# S2ER13.net
KiCad netlist of a schematic drawn in EAGLE
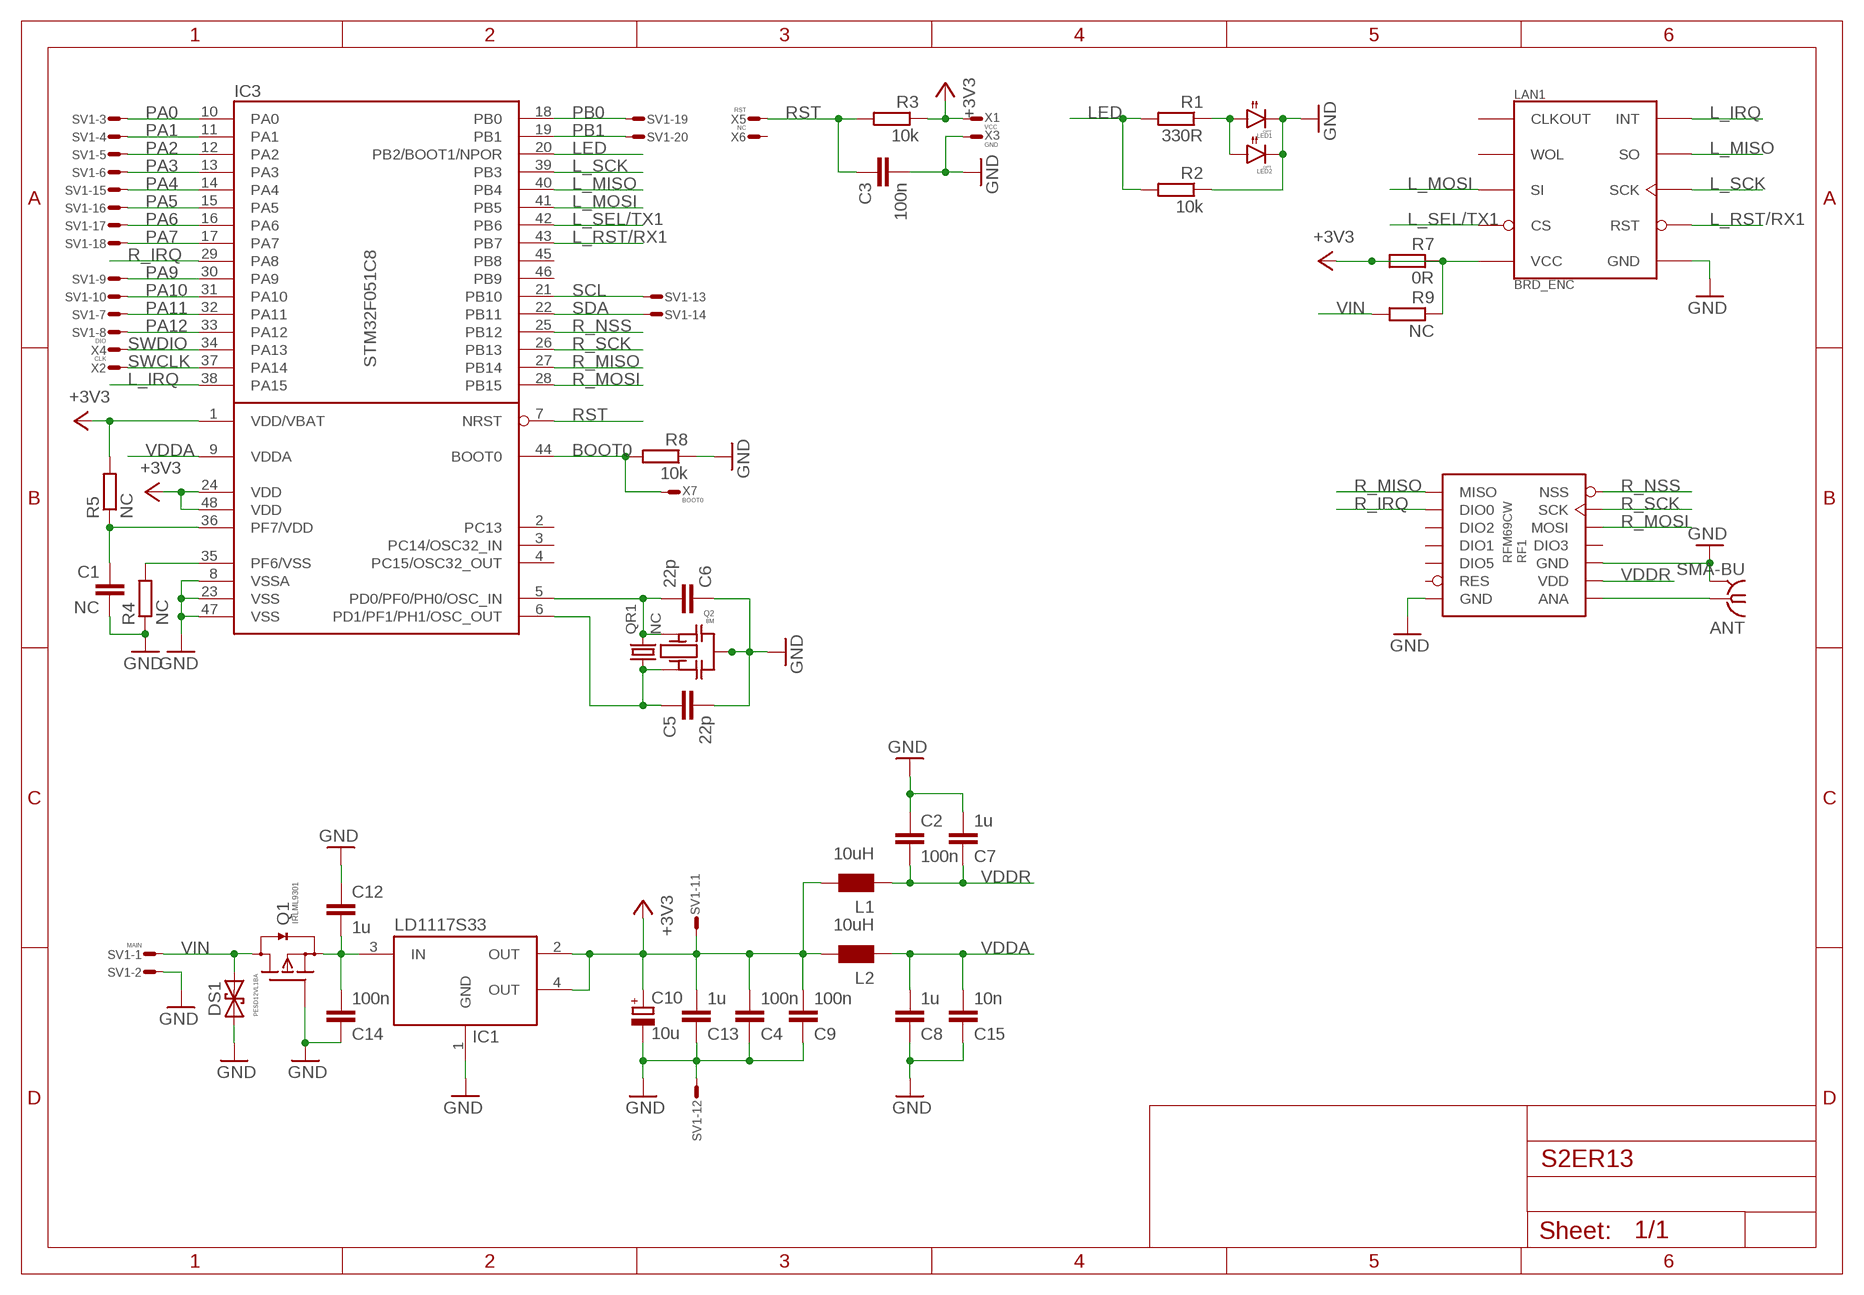
[diagram p0: schematic, sheet 1]

(export (version "E")
  (design (tool "Eeschema 10.0.6"))
  (components
    (comp (ref "ANT")
      (value "SMA-BU")
      (footprint "eagle-import:BU-SMA-V")
      (libsource (lib "eagle-import") (part "SMA-BU"))
    )
    (comp (ref "C1")
      (value "NC")
      (footprint "eagle-import:0603")
      (libsource (lib "eagle-import") (part "C0603"))
    )
    (comp (ref "C2")
      (value "100n")
      (footprint "eagle-import:0603")
      (libsource (lib "eagle-import") (part "C0603"))
    )
    (comp (ref "C3")
      (value "100n")
      (footprint "eagle-import:0603")
      (libsource (lib "eagle-import") (part "C0603"))
    )
    (comp (ref "C4")
      (value "100n")
      (footprint "eagle-import:0603")
      (libsource (lib "eagle-import") (part "C0603"))
    )
    (comp (ref "C5")
      (value "22p")
      (footprint "eagle-import:0603")
      (libsource (lib "eagle-import") (part "C0603"))
    )
    (comp (ref "C6")
      (value "22p")
      (footprint "eagle-import:0603")
      (libsource (lib "eagle-import") (part "C0603"))
    )
    (comp (ref "C7")
      (value "1u")
      (footprint "eagle-import:0603")
      (libsource (lib "eagle-import") (part "C0603"))
    )
    (comp (ref "C8")
      (value "1u")
      (footprint "eagle-import:0603")
      (libsource (lib "eagle-import") (part "C0603"))
    )
    (comp (ref "C9")
      (value "100n")
      (footprint "eagle-import:0603")
      (libsource (lib "eagle-import") (part "C0603"))
    )
    (comp (ref "C10")
      (value "10u")
      (footprint "eagle-import:SMC_A")
      (libsource (lib "eagle-import") (part "C_POLSMCA"))
    )
    (comp (ref "C12")
      (value "1u")
      (footprint "eagle-import:0603")
      (libsource (lib "eagle-import") (part "C0603"))
    )
    (comp (ref "C13")
      (value "1u")
      (footprint "eagle-import:0603")
      (libsource (lib "eagle-import") (part "C0603"))
    )
    (comp (ref "C14")
      (value "100n")
      (footprint "eagle-import:0603")
      (libsource (lib "eagle-import") (part "C0603"))
    )
    (comp (ref "C15")
      (value "10n")
      (footprint "eagle-import:0603")
      (libsource (lib "eagle-import") (part "C0603"))
    )
    (comp (ref "DS1")
      (value "PESD12VL1BA")
      (footprint "eagle-import:SOD323")
      (libsource (lib "eagle-import") (part "TVS-U323"))
    )
    (comp (ref "IC1")
      (value "LD1117S33")
      (footprint "eagle-import:SOT223")
      (libsource (lib "eagle-import") (part "LDO_4P"))
    )
    (comp (ref "IC3")
      (value "STM32F051C8")
      (footprint "eagle-import:LQFP48")
      (libsource (lib "eagle-import") (part "STM32_LQFP48"))
    )
    (comp (ref "L1")
      (value "10uH")
      (footprint "eagle-import:0603")
      (libsource (lib "eagle-import") (part "L0603"))
    )
    (comp (ref "L2")
      (value "10uH")
      (footprint "eagle-import:0603")
      (libsource (lib "eagle-import") (part "L0603"))
    )
    (comp (ref "LAN1")
      (value "BRD_ENC")
      (footprint "eagle-import:BRD_ENC")
      (libsource (lib "eagle-import") (part "BRD_ENC"))
    )
    (comp (ref "LED1")
      (value "OPT")
      (footprint "eagle-import:T1-3_4")
      (libsource (lib "eagle-import") (part "LEDT134"))
    )
    (comp (ref "LED2")
      (value "OPT")
      (footprint "eagle-import:1206")
      (libsource (lib "eagle-import") (part "LED1206"))
    )
    (comp (ref "Q1")
      (value "IRLML9301")
      (footprint "eagle-import:SOT23")
      (libsource (lib "eagle-import") (part "FET-PDSOT23"))
    )
    (comp (ref "Q2")
      (value "8M")
      (footprint "eagle-import:CSTCE")
      (libsource (lib "eagle-import") (part "QRCE"))
    )
    (comp (ref "QR1")
      (value "NC")
      (footprint "eagle-import:ABS07")
      (libsource (lib "eagle-import") (part "QABS07"))
    )
    (comp (ref "R1")
      (value "330R")
      (footprint "eagle-import:0603")
      (libsource (lib "eagle-import") (part "R0603"))
    )
    (comp (ref "R2")
      (value "10k")
      (footprint "eagle-import:0603")
      (libsource (lib "eagle-import") (part "R0603"))
    )
    (comp (ref "R3")
      (value "10k")
      (footprint "eagle-import:0603")
      (libsource (lib "eagle-import") (part "R0603"))
    )
    (comp (ref "R4")
      (value "NC")
      (footprint "eagle-import:0603")
      (libsource (lib "eagle-import") (part "R0603"))
    )
    (comp (ref "R5")
      (value "NC")
      (footprint "eagle-import:0603")
      (libsource (lib "eagle-import") (part "R0603"))
    )
    (comp (ref "R7")
      (value "0R")
      (footprint "eagle-import:0603")
      (libsource (lib "eagle-import") (part "R0603"))
    )
    (comp (ref "R8")
      (value "10k")
      (footprint "eagle-import:0603")
      (libsource (lib "eagle-import") (part "R0603"))
    )
    (comp (ref "R9")
      (value "NC")
      (footprint "eagle-import:0603")
      (libsource (lib "eagle-import") (part "R0603"))
    )
    (comp (ref "RF1")
      (value "RFM69CW")
      (footprint "eagle-import:RFM69CW")
      (libsource (lib "eagle-import") (part "RFM69CWS1-868-"))
    )
    (comp (ref "SV1")
      (value "MAIN")
      (footprint "eagle-import:ML20LS")
      (libsource (lib "eagle-import") (part "ML20?ELS"))
    )
    (comp (ref "X1")
      (value "VCC")
      (footprint "eagle-import:T1.6_0.9")
      (libsource (lib "eagle-import") (part "WIREPADT1.6/0.9"))
    )
    (comp (ref "X2")
      (value "CLK")
      (footprint "eagle-import:T1.6_0.9")
      (libsource (lib "eagle-import") (part "WIREPADT1.6/0.9"))
    )
    (comp (ref "X3")
      (value "GND")
      (footprint "eagle-import:T1.6_0.9")
      (libsource (lib "eagle-import") (part "WIREPADT1.6/0.9"))
    )
    (comp (ref "X4")
      (value "DIO")
      (footprint "eagle-import:T1.6_0.9")
      (libsource (lib "eagle-import") (part "WIREPADT1.6/0.9"))
    )
    (comp (ref "X5")
      (value "RST")
      (footprint "eagle-import:T1.6_0.9")
      (libsource (lib "eagle-import") (part "WIREPADT1.6/0.9"))
    )
    (comp (ref "X6")
      (value "NC")
      (footprint "eagle-import:T1.6_0.9")
      (libsource (lib "eagle-import") (part "WIREPADT1.6/0.9"))
    )
    (comp (ref "X7")
      (value "BOOT0")
      (footprint "eagle-import:T1.6_0.9")
      (libsource (lib "eagle-import") (part "WIREPADT1.6/0.9"))
    )
  )
  (nets
    (net (code "1") (name "+3V3") (class "Default")
      (node (ref "C10") (pin "+") (pinfunction "+_+") (pintype "passive"))
      (node (ref "C13") (pin "2") (pinfunction "2_2") (pintype "passive"))
      (node (ref "C4") (pin "2") (pinfunction "2_2") (pintype "passive"))
      (node (ref "C9") (pin "2") (pinfunction "2_2") (pintype "passive"))
      (node (ref "IC1") (pin "2") (pinfunction "OUT_2") (pintype "bidirectional"))
      (node (ref "IC1") (pin "4") (pinfunction "OUT_4") (pintype "bidirectional"))
      (node (ref "IC3") (pin "1") (pinfunction "VDD/VBAT_1") (pintype "bidirectional"))
      (node (ref "IC3") (pin "24") (pinfunction "VDD_24") (pintype "bidirectional"))
      (node (ref "IC3") (pin "48") (pinfunction "VDD_48") (pintype "bidirectional"))
      (node (ref "L1") (pin "2") (pinfunction "2_2") (pintype "passive"))
      (node (ref "L2") (pin "2") (pinfunction "2_2") (pintype "passive"))
      (node (ref "LAN1") (pin "P$9") (pinfunction "VCC_P$9") (pintype "bidirectional"))
      (node (ref "R3") (pin "1") (pinfunction "1_1") (pintype "passive"))
      (node (ref "R5") (pin "2") (pinfunction "2_2") (pintype "passive"))
      (node (ref "R7") (pin "1") (pinfunction "1_1") (pintype "passive"))
      (node (ref "R7") (pin "2") (pinfunction "2_2") (pintype "passive"))
      (node (ref "R9") (pin "1") (pinfunction "1_1") (pintype "passive"))
      (node (ref "SV1") (pin "P$11") (pinfunction "S_P$11") (pintype "passive"))
      (node (ref "X1") (pin "1") (pinfunction "S_1") (pintype "passive"))
    )
    (net (code "2") (name "/BOOT0") (class "Default")
      (node (ref "IC3") (pin "44") (pinfunction "BOOT0_44") (pintype "bidirectional"))
      (node (ref "R8") (pin "2") (pinfunction "2_2") (pintype "passive"))
      (node (ref "X7") (pin "1") (pinfunction "S_1") (pintype "passive"))
    )
    (net (code "3") (name "/LED") (class "Default")
      (node (ref "IC3") (pin "20") (pinfunction "PB2/BOOT1/NPOR_20") (pintype "bidirectional"))
      (node (ref "R1") (pin "2") (pinfunction "2_2") (pintype "passive"))
      (node (ref "R2") (pin "2") (pinfunction "2_2") (pintype "passive"))
    )
    (net (code "4") (name "/L_IRQ") (class "Default")
      (node (ref "IC3") (pin "38") (pinfunction "PA15_38") (pintype "bidirectional"))
      (node (ref "LAN1") (pin "P$2") (pinfunction "INT_P$2") (pintype "open_collector"))
    )
    (net (code "5") (name "/L_MISO") (class "Default")
      (node (ref "IC3") (pin "40") (pinfunction "PB4_40") (pintype "bidirectional"))
      (node (ref "LAN1") (pin "P$4") (pinfunction "SO_P$4") (pintype "output"))
    )
    (net (code "6") (name "/L_MOSI") (class "Default")
      (node (ref "IC3") (pin "41") (pinfunction "PB5_41") (pintype "bidirectional"))
      (node (ref "LAN1") (pin "P$5") (pinfunction "SI_P$5") (pintype "input"))
    )
    (net (code "7") (name "/L_RST{slash}RX1") (class "Default")
      (node (ref "IC3") (pin "43") (pinfunction "PB7_43") (pintype "bidirectional"))
      (node (ref "LAN1") (pin "P$8") (pinfunction "RST_P$8") (pintype "bidirectional"))
    )
    (net (code "8") (name "/L_SCK") (class "Default")
      (node (ref "IC3") (pin "39") (pinfunction "PB3_39") (pintype "bidirectional"))
      (node (ref "LAN1") (pin "P$6") (pinfunction "SCK_P$6") (pintype "input"))
    )
    (net (code "9") (name "/L_SEL{slash}TX1") (class "Default")
      (node (ref "IC3") (pin "42") (pinfunction "PB6_42") (pintype "bidirectional"))
      (node (ref "LAN1") (pin "P$7") (pinfunction "CS_P$7") (pintype "input"))
    )
    (net (code "10") (name "/PA0") (class "Default")
      (node (ref "IC3") (pin "10") (pinfunction "PA0_10") (pintype "bidirectional"))
      (node (ref "SV1") (pin "P$3") (pinfunction "S_P$3") (pintype "passive"))
    )
    (net (code "11") (name "/PA1") (class "Default")
      (node (ref "IC3") (pin "11") (pinfunction "PA1_11") (pintype "bidirectional"))
      (node (ref "SV1") (pin "P$4") (pinfunction "S_P$4") (pintype "passive"))
    )
    (net (code "12") (name "/PA2") (class "Default")
      (node (ref "IC3") (pin "12") (pinfunction "PA2_12") (pintype "bidirectional"))
      (node (ref "SV1") (pin "P$5") (pinfunction "S_P$5") (pintype "passive"))
    )
    (net (code "13") (name "/PA3") (class "Default")
      (node (ref "IC3") (pin "13") (pinfunction "PA3_13") (pintype "bidirectional"))
      (node (ref "SV1") (pin "P$6") (pinfunction "S_P$6") (pintype "passive"))
    )
    (net (code "14") (name "/PA4") (class "Default")
      (node (ref "IC3") (pin "14") (pinfunction "PA4_14") (pintype "bidirectional"))
      (node (ref "SV1") (pin "P$15") (pinfunction "S_P$15") (pintype "passive"))
    )
    (net (code "15") (name "/PA5") (class "Default")
      (node (ref "IC3") (pin "15") (pinfunction "PA5_15") (pintype "bidirectional"))
      (node (ref "SV1") (pin "P$16") (pinfunction "S_P$16") (pintype "passive"))
    )
    (net (code "16") (name "/PA6") (class "Default")
      (node (ref "IC3") (pin "16") (pinfunction "PA6_16") (pintype "bidirectional"))
      (node (ref "SV1") (pin "P$17") (pinfunction "S_P$17") (pintype "passive"))
    )
    (net (code "17") (name "/PA7") (class "Default")
      (node (ref "IC3") (pin "17") (pinfunction "PA7_17") (pintype "bidirectional"))
      (node (ref "SV1") (pin "P$18") (pinfunction "S_P$18") (pintype "passive"))
    )
    (net (code "18") (name "/PA9") (class "Default")
      (node (ref "IC3") (pin "30") (pinfunction "PA9_30") (pintype "bidirectional"))
      (node (ref "SV1") (pin "P$9") (pinfunction "S_P$9") (pintype "passive"))
    )
    (net (code "19") (name "/PA10") (class "Default")
      (node (ref "IC3") (pin "31") (pinfunction "PA10_31") (pintype "bidirectional"))
      (node (ref "SV1") (pin "P$10") (pinfunction "S_P$10") (pintype "passive"))
    )
    (net (code "20") (name "/PA11") (class "Default")
      (node (ref "IC3") (pin "32") (pinfunction "PA11_32") (pintype "bidirectional"))
      (node (ref "SV1") (pin "P$7") (pinfunction "S_P$7") (pintype "passive"))
    )
    (net (code "21") (name "/PA12") (class "Default")
      (node (ref "IC3") (pin "33") (pinfunction "PA12_33") (pintype "bidirectional"))
      (node (ref "SV1") (pin "P$8") (pinfunction "S_P$8") (pintype "passive"))
    )
    (net (code "22") (name "/PB0") (class "Default")
      (node (ref "IC3") (pin "18") (pinfunction "PB0_18") (pintype "bidirectional"))
      (node (ref "SV1") (pin "P$19") (pinfunction "S_P$19") (pintype "passive"))
    )
    (net (code "23") (name "/PB1") (class "Default")
      (node (ref "IC3") (pin "19") (pinfunction "PB1_19") (pintype "bidirectional"))
      (node (ref "SV1") (pin "P$20") (pinfunction "S_P$20") (pintype "passive"))
    )
    (net (code "24") (name "/RST") (class "Default")
      (node (ref "C3") (pin "1") (pinfunction "1_1") (pintype "passive"))
      (node (ref "IC3") (pin "7") (pinfunction "NRST_7") (pintype "bidirectional"))
      (node (ref "R3") (pin "2") (pinfunction "2_2") (pintype "passive"))
      (node (ref "X5") (pin "1") (pinfunction "S_1") (pintype "passive"))
    )
    (net (code "25") (name "/R_IRQ") (class "Default")
      (node (ref "IC3") (pin "29") (pinfunction "PA8_29") (pintype "bidirectional"))
      (node (ref "RF1") (pin "DIO0") (pinfunction "DIO0_DIO0") (pintype "bidirectional"))
    )
    (net (code "26") (name "/R_MISO") (class "Default")
      (node (ref "IC3") (pin "27") (pinfunction "PB14_27") (pintype "bidirectional"))
      (node (ref "RF1") (pin "MISO") (pinfunction "MISO_MISO") (pintype "output"))
    )
    (net (code "27") (name "/R_MOSI") (class "Default")
      (node (ref "IC3") (pin "28") (pinfunction "PB15_28") (pintype "bidirectional"))
      (node (ref "RF1") (pin "MOSI") (pinfunction "MOSI_MOSI") (pintype "input"))
    )
    (net (code "28") (name "/R_NSS") (class "Default")
      (node (ref "IC3") (pin "25") (pinfunction "PB12_25") (pintype "bidirectional"))
      (node (ref "RF1") (pin "NSS") (pinfunction "NSS_NSS") (pintype "input"))
    )
    (net (code "29") (name "/R_SCK") (class "Default")
      (node (ref "IC3") (pin "26") (pinfunction "PB13_26") (pintype "bidirectional"))
      (node (ref "RF1") (pin "SCK") (pinfunction "SCK_SCK") (pintype "input"))
    )
    (net (code "30") (name "/SCL") (class "Default")
      (node (ref "IC3") (pin "21") (pinfunction "PB10_21") (pintype "bidirectional"))
      (node (ref "SV1") (pin "P$13") (pinfunction "S_P$13") (pintype "passive"))
    )
    (net (code "31") (name "/SDA") (class "Default")
      (node (ref "IC3") (pin "22") (pinfunction "PB11_22") (pintype "bidirectional"))
      (node (ref "SV1") (pin "P$14") (pinfunction "S_P$14") (pintype "passive"))
    )
    (net (code "32") (name "/SWCLK") (class "Default")
      (node (ref "IC3") (pin "37") (pinfunction "PA14_37") (pintype "bidirectional"))
      (node (ref "X2") (pin "1") (pinfunction "S_1") (pintype "passive"))
    )
    (net (code "33") (name "/SWDIO") (class "Default")
      (node (ref "IC3") (pin "34") (pinfunction "PA13_34") (pintype "bidirectional"))
      (node (ref "X4") (pin "1") (pinfunction "S_1") (pintype "passive"))
    )
    (net (code "34") (name "/VDDA") (class "Default")
      (node (ref "C15") (pin "2") (pinfunction "2_2") (pintype "passive"))
      (node (ref "C8") (pin "2") (pinfunction "2_2") (pintype "passive"))
      (node (ref "IC3") (pin "9") (pinfunction "VDDA_9") (pintype "bidirectional"))
      (node (ref "L2") (pin "1") (pinfunction "1_1") (pintype "passive"))
    )
    (net (code "35") (name "/VDDR") (class "Default")
      (node (ref "C2") (pin "2") (pinfunction "2_2") (pintype "passive"))
      (node (ref "C7") (pin "1") (pinfunction "1_1") (pintype "passive"))
      (node (ref "L1") (pin "1") (pinfunction "1_1") (pintype "passive"))
      (node (ref "RF1") (pin "VDD") (pinfunction "VDD_VDD") (pintype "power_in"))
    )
    (net (code "36") (name "/VIN") (class "Default")
      (node (ref "DS1") (pin "C") (pinfunction "2_C") (pintype "passive"))
      (node (ref "Q1") (pin "3") (pinfunction "D_3") (pintype "passive"))
      (node (ref "R9") (pin "2") (pinfunction "2_2") (pintype "passive"))
      (node (ref "SV1") (pin "P$1") (pinfunction "S_P$1") (pintype "passive"))
    )
    (net (code "37") (name "GND") (class "Default")
      (node (ref "ANT") (pin "2") (pinfunction "2_2") (pintype "passive"))
      (node (ref "ANT") (pin "3") (pinfunction "2_3") (pintype "passive"))
      (node (ref "ANT") (pin "4") (pinfunction "2_4") (pintype "passive"))
      (node (ref "ANT") (pin "5") (pinfunction "2_5") (pintype "passive"))
      (node (ref "C1") (pin "2") (pinfunction "2_2") (pintype "passive"))
      (node (ref "C10") (pin "-") (pinfunction "-_-") (pintype "passive"))
      (node (ref "C12") (pin "1") (pinfunction "1_1") (pintype "passive"))
      (node (ref "C13") (pin "1") (pinfunction "1_1") (pintype "passive"))
      (node (ref "C14") (pin "1") (pinfunction "1_1") (pintype "passive"))
      (node (ref "C15") (pin "1") (pinfunction "1_1") (pintype "passive"))
      (node (ref "C2") (pin "1") (pinfunction "1_1") (pintype "passive"))
      (node (ref "C3") (pin "2") (pinfunction "2_2") (pintype "passive"))
      (node (ref "C4") (pin "1") (pinfunction "1_1") (pintype "passive"))
      (node (ref "C5") (pin "2") (pinfunction "2_2") (pintype "passive"))
      (node (ref "C6") (pin "1") (pinfunction "1_1") (pintype "passive"))
      (node (ref "C7") (pin "2") (pinfunction "2_2") (pintype "passive"))
      (node (ref "C8") (pin "1") (pinfunction "1_1") (pintype "passive"))
      (node (ref "C9") (pin "1") (pinfunction "1_1") (pintype "passive"))
      (node (ref "DS1") (pin "A") (pinfunction "1_A") (pintype "passive"))
      (node (ref "IC1") (pin "1") (pinfunction "GND_1") (pintype "bidirectional"))
      (node (ref "IC3") (pin "23") (pinfunction "VSS_23") (pintype "bidirectional"))
      (node (ref "IC3") (pin "47") (pinfunction "VSS_47") (pintype "bidirectional"))
      (node (ref "IC3") (pin "8") (pinfunction "VSSA_8") (pintype "bidirectional"))
      (node (ref "LAN1") (pin "P$10") (pinfunction "GND_P$10") (pintype "bidirectional"))
      (node (ref "LED1") (pin "C") (pinfunction "C_C") (pintype "bidirectional"))
      (node (ref "LED2") (pin "2") (pinfunction "C_2") (pintype "bidirectional"))
      (node (ref "Q1") (pin "1") (pinfunction "G_1") (pintype "passive"))
      (node (ref "Q2") (pin "G") (pinfunction "M_G") (pintype "passive"))
      (node (ref "R2") (pin "1") (pinfunction "1_1") (pintype "passive"))
      (node (ref "R4") (pin "1") (pinfunction "1_1") (pintype "passive"))
      (node (ref "R8") (pin "1") (pinfunction "1_1") (pintype "passive"))
      (node (ref "RF1") (pin "GND@14") (pinfunction "GND_GND@14") (pintype "power_in"))
      (node (ref "RF1") (pin "GND@3") (pinfunction "GND_GND@3") (pintype "power_in"))
      (node (ref "SV1") (pin "P$12") (pinfunction "S_P$12") (pintype "passive"))
      (node (ref "SV1") (pin "P$2") (pinfunction "S_P$2") (pintype "passive"))
      (node (ref "X3") (pin "1") (pinfunction "S_1") (pintype "passive"))
    )
    (net (code "38") (name "Net-(ANT-Pad1)") (class "Default")
      (node (ref "ANT") (pin "1") (pinfunction "1_1") (pintype "passive"))
      (node (ref "RF1") (pin "ANA") (pinfunction "ANA_ANA") (pintype "passive"))
    )
    (net (code "39") (name "Net-(IC1-IN)") (class "Default")
      (node (ref "C12") (pin "2") (pinfunction "2_2") (pintype "passive"))
      (node (ref "C14") (pin "2") (pinfunction "2_2") (pintype "passive"))
      (node (ref "IC1") (pin "3") (pinfunction "IN_3") (pintype "bidirectional"))
      (node (ref "Q1") (pin "2") (pinfunction "S_2") (pintype "passive"))
    )
    (net (code "40") (name "Net-(IC3-PD0{slash}PF0{slash}PH0{slash}OSC_IN)") (class "Default")
      (node (ref "C6") (pin "2") (pinfunction "2_2") (pintype "passive"))
      (node (ref "IC3") (pin "5") (pinfunction "PD0/PF0/PH0/OSC_IN_5") (pintype "bidirectional"))
      (node (ref "Q2") (pin "A") (pinfunction "1_A") (pintype "passive"))
      (node (ref "QR1") (pin "P$2") (pinfunction "2_P$2") (pintype "passive"))
    )
    (net (code "41") (name "Net-(IC3-PD1{slash}PF1{slash}PH1{slash}OSC_OUT)") (class "Default")
      (node (ref "C5") (pin "1") (pinfunction "1_1") (pintype "passive"))
      (node (ref "IC3") (pin "6") (pinfunction "PD1/PF1/PH1/OSC_OUT_6") (pintype "bidirectional"))
      (node (ref "Q2") (pin "B") (pinfunction "2_B") (pintype "passive"))
      (node (ref "QR1") (pin "P$1") (pinfunction "1_P$1") (pintype "passive"))
    )
    (net (code "42") (name "Net-(IC3-PF6{slash}VSS)") (class "Default")
      (node (ref "IC3") (pin "35") (pinfunction "PF6/VSS_35") (pintype "bidirectional"))
      (node (ref "R4") (pin "2") (pinfunction "2_2") (pintype "passive"))
    )
    (net (code "43") (name "Net-(IC3-PF7{slash}VDD)") (class "Default")
      (node (ref "C1") (pin "1") (pinfunction "1_1") (pintype "passive"))
      (node (ref "IC3") (pin "36") (pinfunction "PF7/VDD_36") (pintype "bidirectional"))
      (node (ref "R5") (pin "1") (pinfunction "1_1") (pintype "passive"))
    )
    (net (code "44") (name "Net-(LED2-A)") (class "Default")
      (node (ref "LED1") (pin "A") (pinfunction "A_A") (pintype "bidirectional"))
      (node (ref "LED2") (pin "1") (pinfunction "A_1") (pintype "bidirectional"))
      (node (ref "R1") (pin "1") (pinfunction "1_1") (pintype "passive"))
    )
    (net (code "45") (name "unconnected-(IC3-PB8-Pad45)") (class "Default")
      (node (ref "IC3") (pin "45") (pinfunction "PB8_45") (pintype "bidirectional"))
    )
    (net (code "46") (name "unconnected-(IC3-PB9-Pad46)") (class "Default")
      (node (ref "IC3") (pin "46") (pinfunction "PB9_46") (pintype "bidirectional"))
    )
    (net (code "47") (name "unconnected-(IC3-PC13-Pad2)") (class "Default")
      (node (ref "IC3") (pin "2") (pinfunction "PC13_2") (pintype "bidirectional"))
    )
    (net (code "48") (name "unconnected-(IC3-PC14{slash}OSC32_IN-Pad3)") (class "Default")
      (node (ref "IC3") (pin "3") (pinfunction "PC14/OSC32_IN_3") (pintype "bidirectional"))
    )
    (net (code "49") (name "unconnected-(IC3-PC15{slash}OSC32_OUT-Pad4)") (class "Default")
      (node (ref "IC3") (pin "4") (pinfunction "PC15/OSC32_OUT_4") (pintype "bidirectional"))
    )
    (net (code "50") (name "unconnected-(LAN1-CLKOUT-PadP$1)") (class "Default")
      (node (ref "LAN1") (pin "P$1") (pinfunction "CLKOUT_P$1") (pintype "output"))
    )
    (net (code "51") (name "unconnected-(LAN1-WOL-PadP$3)") (class "Default")
      (node (ref "LAN1") (pin "P$3") (pinfunction "WOL_P$3") (pintype "output"))
    )
    (net (code "52") (name "unconnected-(RF1-PadDIO1)") (class "Default")
      (node (ref "RF1") (pin "DIO1") (pinfunction "DIO1_DIO1") (pintype "bidirectional"))
    )
    (net (code "53") (name "unconnected-(RF1-PadDIO2)") (class "Default")
      (node (ref "RF1") (pin "DIO2") (pinfunction "DIO2_DIO2") (pintype "bidirectional"))
    )
    (net (code "54") (name "unconnected-(RF1-PadDIO3)") (class "Default")
      (node (ref "RF1") (pin "DIO3") (pinfunction "DIO3_DIO3") (pintype "bidirectional"))
    )
    (net (code "55") (name "unconnected-(RF1-PadDIO5)") (class "Default")
      (node (ref "RF1") (pin "DIO5") (pinfunction "DIO5_DIO5") (pintype "output"))
    )
    (net (code "56") (name "unconnected-(RF1-RES-Pad{slash}RES)") (class "Default")
      (node (ref "RF1") (pin "/RES") (pinfunction "RES_/RES") (pintype "bidirectional"))
    )
    (net (code "57") (name "unconnected-(X6-S-Pad1)") (class "Default")
      (node (ref "X6") (pin "1") (pinfunction "S_1") (pintype "passive"))
    )
  )
)
